# DA_uno_shield_0_2.net
KiCad netlist of a schematic drawn in EAGLE
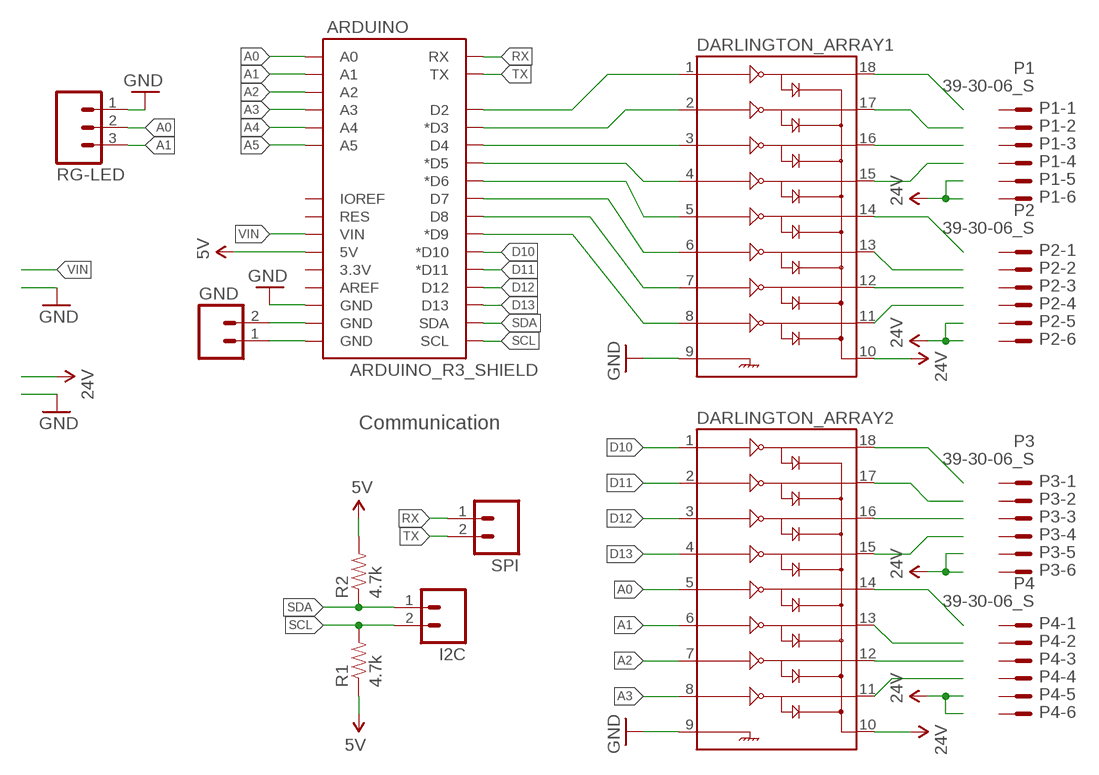
[diagram p0: schematic, sheet 1]

(export (version "E")
  (design (tool "Eeschema 10.0.6"))
  (components
    (comp (ref "ARDUINO")
      (value "ARDUINO_R3_SHIELD")
      (footprint "eagle-import:UNO_R3_SHIELD")
      (libsource (lib "eagle-import") (part "ARDUINO_R3_SHIELD"))
    )
    (comp (ref "DARLINGTON_ARRAY1")
      (value "ULN2803DIP")
      (footprint "eagle-import:DIL18")
      (libsource (lib "eagle-import") (part "ULN2803DIP"))
    )
    (comp (ref "DARLINGTON_ARRAY2")
      (value "ULN2803DIP")
      (footprint "eagle-import:DIL18")
      (libsource (lib "eagle-import") (part "ULN2803DIP"))
    )
    (comp (ref "GND")
      (value "M02LOCK_LONGPADS")
      (footprint "eagle-import:1X02_LOCK_LONGPADS")
      (libsource (lib "eagle-import") (part "M02LOCK_LONGPADS"))
    )
    (comp (ref "I2C")
      (value "M02LOCK_LONGPADS")
      (footprint "eagle-import:1X02_LOCK_LONGPADS")
      (libsource (lib "eagle-import") (part "M02LOCK_LONGPADS"))
    )
    (comp (ref "P1")
      (value "39-30-06_S")
      (footprint "eagle-import:39-30-_06_")
      (libsource (lib "eagle-import") (part "39-30-?06?_S"))
    )
    (comp (ref "P2")
      (value "39-30-06_S")
      (footprint "eagle-import:39-30-_06_")
      (libsource (lib "eagle-import") (part "39-30-?06?_S"))
    )
    (comp (ref "P3")
      (value "39-30-06_S")
      (footprint "eagle-import:39-30-_06_")
      (libsource (lib "eagle-import") (part "39-30-?06?_S"))
    )
    (comp (ref "P4")
      (value "39-30-06_S")
      (footprint "eagle-import:39-30-_06_")
      (libsource (lib "eagle-import") (part "39-30-?06?_S"))
    )
    (comp (ref "R1")
      (value "4.7k")
      (footprint "eagle-import:AXIAL-0.3-KIT")
      (libsource (lib "eagle-import") (part "RESISTORKIT"))
    )
    (comp (ref "R2")
      (value "4.7k")
      (footprint "eagle-import:AXIAL-0.3-KIT")
      (libsource (lib "eagle-import") (part "RESISTORKIT"))
    )
    (comp (ref "RG-LED")
      (value "M03LONGPADS")
      (footprint "eagle-import:1X03_LONGPADS")
      (libsource (lib "eagle-import") (part "M03LONGPADS"))
    )
    (comp (ref "SPI")
      (value "M02LOCK_LONGPADS")
      (footprint "eagle-import:1X02_LOCK_LONGPADS")
      (libsource (lib "eagle-import") (part "M02LOCK_LONGPADS"))
    )
  )
  (nets
    (net (code "1") (name "5V") (class "Default")
      (node (ref "ARDUINO") (pin "5V") (pinfunction "5V_5V") (pintype "bidirectional"))
      (node (ref "R1") (pin "P$1") (pinfunction "1_P$1") (pintype "passive"))
      (node (ref "R2") (pin "P$2") (pinfunction "2_P$2") (pintype "passive"))
    )
    (net (code "2") (name "24V") (class "Default")
      (node (ref "DARLINGTON_ARRAY1") (pin "10") (pinfunction "10_10") (pintype "bidirectional"))
      (node (ref "DARLINGTON_ARRAY2") (pin "10") (pinfunction "10_10") (pintype "bidirectional"))
    )
    (net (code "3") (name "A0") (class "Default")
      (node (ref "ARDUINO") (pin "A0") (pinfunction "A0_A0") (pintype "bidirectional"))
      (node (ref "DARLINGTON_ARRAY2") (pin "5") (pinfunction "5_5") (pintype "bidirectional"))
      (node (ref "RG-LED") (pin "2") (pinfunction "2_2") (pintype "passive"))
    )
    (net (code "4") (name "A1") (class "Default")
      (node (ref "ARDUINO") (pin "A1") (pinfunction "A1_A1") (pintype "bidirectional"))
      (node (ref "DARLINGTON_ARRAY2") (pin "6") (pinfunction "6_6") (pintype "bidirectional"))
      (node (ref "RG-LED") (pin "3") (pinfunction "3_3") (pintype "passive"))
    )
    (net (code "5") (name "A2") (class "Default")
      (node (ref "ARDUINO") (pin "A2") (pinfunction "A2_A2") (pintype "bidirectional"))
      (node (ref "DARLINGTON_ARRAY2") (pin "7") (pinfunction "7_7") (pintype "bidirectional"))
    )
    (net (code "6") (name "A3") (class "Default")
      (node (ref "ARDUINO") (pin "A3") (pinfunction "A3_A3") (pintype "bidirectional"))
      (node (ref "DARLINGTON_ARRAY2") (pin "8") (pinfunction "8_8") (pintype "bidirectional"))
    )
    (net (code "7") (name "A4") (class "Default")
      (node (ref "ARDUINO") (pin "A4") (pinfunction "A4_A4") (pintype "bidirectional"))
    )
    (net (code "8") (name "A5") (class "Default")
      (node (ref "ARDUINO") (pin "A5") (pinfunction "A5_A5") (pintype "bidirectional"))
    )
    (net (code "9") (name "D10") (class "Default")
      (node (ref "ARDUINO") (pin "D10") (pinfunction "*D10_D10") (pintype "bidirectional"))
      (node (ref "DARLINGTON_ARRAY2") (pin "1") (pinfunction "1_1") (pintype "bidirectional"))
    )
    (net (code "10") (name "D11") (class "Default")
      (node (ref "ARDUINO") (pin "D11") (pinfunction "*D11_D11") (pintype "bidirectional"))
      (node (ref "DARLINGTON_ARRAY2") (pin "2") (pinfunction "2_2") (pintype "bidirectional"))
    )
    (net (code "11") (name "D12") (class "Default")
      (node (ref "ARDUINO") (pin "D12") (pinfunction "D12_D12") (pintype "bidirectional"))
      (node (ref "DARLINGTON_ARRAY2") (pin "3") (pinfunction "3_3") (pintype "bidirectional"))
    )
    (net (code "12") (name "D13") (class "Default")
      (node (ref "ARDUINO") (pin "D13") (pinfunction "D13_D13") (pintype "bidirectional"))
      (node (ref "DARLINGTON_ARRAY2") (pin "4") (pinfunction "4_4") (pintype "bidirectional"))
    )
    (net (code "13") (name "GND") (class "Default")
      (node (ref "ARDUINO") (pin "GND@2") (pinfunction "GND_GND@2") (pintype "bidirectional"))
      (node (ref "DARLINGTON_ARRAY1") (pin "9") (pinfunction "9_9") (pintype "bidirectional"))
      (node (ref "DARLINGTON_ARRAY2") (pin "9") (pinfunction "9_9") (pintype "bidirectional"))
      (node (ref "RG-LED") (pin "1") (pinfunction "1_1") (pintype "passive"))
    )
    (net (code "14") (name "Net-(ARDUINO-*D3)") (class "Default")
      (node (ref "ARDUINO") (pin "D3") (pinfunction "*D3_D3") (pintype "bidirectional"))
      (node (ref "DARLINGTON_ARRAY1") (pin "2") (pinfunction "2_2") (pintype "bidirectional"))
    )
    (net (code "15") (name "Net-(ARDUINO-*D5)") (class "Default")
      (node (ref "ARDUINO") (pin "D5") (pinfunction "*D5_D5") (pintype "bidirectional"))
      (node (ref "DARLINGTON_ARRAY1") (pin "4") (pinfunction "4_4") (pintype "bidirectional"))
    )
    (net (code "16") (name "Net-(ARDUINO-*D6)") (class "Default")
      (node (ref "ARDUINO") (pin "D6") (pinfunction "*D6_D6") (pintype "bidirectional"))
      (node (ref "DARLINGTON_ARRAY1") (pin "5") (pinfunction "5_5") (pintype "bidirectional"))
    )
    (net (code "17") (name "Net-(ARDUINO-*D9)") (class "Default")
      (node (ref "ARDUINO") (pin "D9") (pinfunction "*D9_D9") (pintype "bidirectional"))
      (node (ref "DARLINGTON_ARRAY1") (pin "8") (pinfunction "8_8") (pintype "bidirectional"))
    )
    (net (code "18") (name "Net-(ARDUINO-GND-PadGND@0)") (class "Default")
      (node (ref "ARDUINO") (pin "GND@0") (pinfunction "GND_GND@0") (pintype "bidirectional"))
      (node (ref "GND") (pin "1") (pinfunction "1_1") (pintype "passive"))
    )
    (net (code "19") (name "Net-(ARDUINO-GND-PadGND@1)") (class "Default")
      (node (ref "ARDUINO") (pin "GND@1") (pinfunction "GND_GND@1") (pintype "bidirectional"))
      (node (ref "GND") (pin "2") (pinfunction "2_2") (pintype "passive"))
    )
    (net (code "20") (name "Net-(ARDUINO-PadD2)") (class "Default")
      (node (ref "ARDUINO") (pin "D2") (pinfunction "D2_D2") (pintype "bidirectional"))
      (node (ref "DARLINGTON_ARRAY1") (pin "1") (pinfunction "1_1") (pintype "bidirectional"))
    )
    (net (code "21") (name "Net-(ARDUINO-PadD4)") (class "Default")
      (node (ref "ARDUINO") (pin "D4") (pinfunction "D4_D4") (pintype "bidirectional"))
      (node (ref "DARLINGTON_ARRAY1") (pin "3") (pinfunction "3_3") (pintype "bidirectional"))
    )
    (net (code "22") (name "Net-(ARDUINO-PadD7)") (class "Default")
      (node (ref "ARDUINO") (pin "D7") (pinfunction "D7_D7") (pintype "bidirectional"))
      (node (ref "DARLINGTON_ARRAY1") (pin "6") (pinfunction "6_6") (pintype "bidirectional"))
    )
    (net (code "23") (name "Net-(ARDUINO-PadD8)") (class "Default")
      (node (ref "ARDUINO") (pin "D8") (pinfunction "D8_D8") (pintype "bidirectional"))
      (node (ref "DARLINGTON_ARRAY1") (pin "7") (pinfunction "7_7") (pintype "bidirectional"))
    )
    (net (code "24") (name "RX") (class "Default")
      (node (ref "ARDUINO") (pin "RX") (pinfunction "RX_RX") (pintype "bidirectional"))
      (node (ref "SPI") (pin "1") (pinfunction "1_1") (pintype "passive"))
    )
    (net (code "25") (name "SCL") (class "Default")
      (node (ref "ARDUINO") (pin "SCL") (pinfunction "SCL_SCL") (pintype "bidirectional"))
      (node (ref "I2C") (pin "2") (pinfunction "2_2") (pintype "passive"))
      (node (ref "R1") (pin "P$2") (pinfunction "2_P$2") (pintype "passive"))
    )
    (net (code "26") (name "SDA") (class "Default")
      (node (ref "ARDUINO") (pin "SDA") (pinfunction "SDA_SDA") (pintype "bidirectional"))
      (node (ref "I2C") (pin "1") (pinfunction "1_1") (pintype "passive"))
      (node (ref "R2") (pin "P$1") (pinfunction "1_P$1") (pintype "passive"))
    )
    (net (code "27") (name "TX") (class "Default")
      (node (ref "ARDUINO") (pin "TX") (pinfunction "TX_TX") (pintype "bidirectional"))
      (node (ref "SPI") (pin "2") (pinfunction "2_2") (pintype "passive"))
    )
    (net (code "28") (name "VIN") (class "Default")
      (node (ref "ARDUINO") (pin "VIN") (pinfunction "VIN_VIN") (pintype "bidirectional"))
    )
    (net (code "29") (name "unconnected-(ARDUINO-Pad3.3V)") (class "Default")
      (node (ref "ARDUINO") (pin "3.3V") (pinfunction "3.3V_3.3V") (pintype "bidirectional"))
    )
    (net (code "30") (name "unconnected-(ARDUINO-PadAREF)") (class "Default")
      (node (ref "ARDUINO") (pin "AREF") (pinfunction "AREF_AREF") (pintype "bidirectional"))
    )
    (net (code "31") (name "unconnected-(ARDUINO-PadIOREF)") (class "Default")
      (node (ref "ARDUINO") (pin "IOREF") (pinfunction "IOREF_IOREF") (pintype "bidirectional"))
    )
    (net (code "32") (name "unconnected-(ARDUINO-PadRES)") (class "Default")
      (node (ref "ARDUINO") (pin "RES") (pinfunction "RES_RES") (pintype "bidirectional"))
    )
    (net (code "33") (name "unconnected-(DARLINGTON_ARRAY1-Pad11)") (class "Default")
      (node (ref "DARLINGTON_ARRAY1") (pin "11") (pinfunction "11_11") (pintype "bidirectional"))
    )
    (net (code "34") (name "unconnected-(DARLINGTON_ARRAY1-Pad12)") (class "Default")
      (node (ref "DARLINGTON_ARRAY1") (pin "12") (pinfunction "12_12") (pintype "bidirectional"))
    )
    (net (code "35") (name "unconnected-(DARLINGTON_ARRAY1-Pad13)") (class "Default")
      (node (ref "DARLINGTON_ARRAY1") (pin "13") (pinfunction "13_13") (pintype "bidirectional"))
    )
    (net (code "36") (name "unconnected-(DARLINGTON_ARRAY1-Pad14)") (class "Default")
      (node (ref "DARLINGTON_ARRAY1") (pin "14") (pinfunction "14_14") (pintype "bidirectional"))
    )
    (net (code "37") (name "unconnected-(DARLINGTON_ARRAY1-Pad15)") (class "Default")
      (node (ref "DARLINGTON_ARRAY1") (pin "15") (pinfunction "15_15") (pintype "bidirectional"))
    )
    (net (code "38") (name "unconnected-(DARLINGTON_ARRAY1-Pad16)") (class "Default")
      (node (ref "DARLINGTON_ARRAY1") (pin "16") (pinfunction "16_16") (pintype "bidirectional"))
    )
    (net (code "39") (name "unconnected-(DARLINGTON_ARRAY1-Pad17)") (class "Default")
      (node (ref "DARLINGTON_ARRAY1") (pin "17") (pinfunction "17_17") (pintype "bidirectional"))
    )
    (net (code "40") (name "unconnected-(DARLINGTON_ARRAY1-Pad18)") (class "Default")
      (node (ref "DARLINGTON_ARRAY1") (pin "18") (pinfunction "18_18") (pintype "bidirectional"))
    )
    (net (code "41") (name "unconnected-(DARLINGTON_ARRAY2-Pad11)") (class "Default")
      (node (ref "DARLINGTON_ARRAY2") (pin "11") (pinfunction "11_11") (pintype "bidirectional"))
    )
    (net (code "42") (name "unconnected-(DARLINGTON_ARRAY2-Pad12)") (class "Default")
      (node (ref "DARLINGTON_ARRAY2") (pin "12") (pinfunction "12_12") (pintype "bidirectional"))
    )
    (net (code "43") (name "unconnected-(DARLINGTON_ARRAY2-Pad13)") (class "Default")
      (node (ref "DARLINGTON_ARRAY2") (pin "13") (pinfunction "13_13") (pintype "bidirectional"))
    )
    (net (code "44") (name "unconnected-(DARLINGTON_ARRAY2-Pad14)") (class "Default")
      (node (ref "DARLINGTON_ARRAY2") (pin "14") (pinfunction "14_14") (pintype "bidirectional"))
    )
    (net (code "45") (name "unconnected-(DARLINGTON_ARRAY2-Pad15)") (class "Default")
      (node (ref "DARLINGTON_ARRAY2") (pin "15") (pinfunction "15_15") (pintype "bidirectional"))
    )
    (net (code "46") (name "unconnected-(DARLINGTON_ARRAY2-Pad16)") (class "Default")
      (node (ref "DARLINGTON_ARRAY2") (pin "16") (pinfunction "16_16") (pintype "bidirectional"))
    )
    (net (code "47") (name "unconnected-(DARLINGTON_ARRAY2-Pad17)") (class "Default")
      (node (ref "DARLINGTON_ARRAY2") (pin "17") (pinfunction "17_17") (pintype "bidirectional"))
    )
    (net (code "48") (name "unconnected-(DARLINGTON_ARRAY2-Pad18)") (class "Default")
      (node (ref "DARLINGTON_ARRAY2") (pin "18") (pinfunction "18_18") (pintype "bidirectional"))
    )
    (net (code "49") (name "unconnected-(P1A-P-Pad1)") (class "Default")
      (node (ref "P1") (pin "1") (pinfunction "P_1") (pintype "passive"))
    )
    (net (code "50") (name "unconnected-(P1B-P-Pad2)") (class "Default")
      (node (ref "P1") (pin "2") (pinfunction "P_2") (pintype "passive"))
    )
    (net (code "51") (name "unconnected-(P1C-P-Pad3)") (class "Default")
      (node (ref "P1") (pin "3") (pinfunction "P_3") (pintype "passive"))
    )
    (net (code "52") (name "unconnected-(P1D-P-Pad4)") (class "Default")
      (node (ref "P1") (pin "4") (pinfunction "P_4") (pintype "passive"))
    )
    (net (code "53") (name "unconnected-(P1E-P-Pad5)") (class "Default")
      (node (ref "P1") (pin "5") (pinfunction "P_5") (pintype "passive"))
    )
    (net (code "54") (name "unconnected-(P1F-P-Pad6)") (class "Default")
      (node (ref "P1") (pin "6") (pinfunction "P_6") (pintype "passive"))
    )
    (net (code "55") (name "unconnected-(P2A-P-Pad1)") (class "Default")
      (node (ref "P2") (pin "1") (pinfunction "P_1") (pintype "passive"))
    )
    (net (code "56") (name "unconnected-(P2B-P-Pad2)") (class "Default")
      (node (ref "P2") (pin "2") (pinfunction "P_2") (pintype "passive"))
    )
    (net (code "57") (name "unconnected-(P2C-P-Pad3)") (class "Default")
      (node (ref "P2") (pin "3") (pinfunction "P_3") (pintype "passive"))
    )
    (net (code "58") (name "unconnected-(P2D-P-Pad4)") (class "Default")
      (node (ref "P2") (pin "4") (pinfunction "P_4") (pintype "passive"))
    )
    (net (code "59") (name "unconnected-(P2E-P-Pad5)") (class "Default")
      (node (ref "P2") (pin "5") (pinfunction "P_5") (pintype "passive"))
    )
    (net (code "60") (name "unconnected-(P2F-P-Pad6)") (class "Default")
      (node (ref "P2") (pin "6") (pinfunction "P_6") (pintype "passive"))
    )
    (net (code "61") (name "unconnected-(P3A-P-Pad1)") (class "Default")
      (node (ref "P3") (pin "1") (pinfunction "P_1") (pintype "passive"))
    )
    (net (code "62") (name "unconnected-(P3B-P-Pad2)") (class "Default")
      (node (ref "P3") (pin "2") (pinfunction "P_2") (pintype "passive"))
    )
    (net (code "63") (name "unconnected-(P3C-P-Pad3)") (class "Default")
      (node (ref "P3") (pin "3") (pinfunction "P_3") (pintype "passive"))
    )
    (net (code "64") (name "unconnected-(P3D-P-Pad4)") (class "Default")
      (node (ref "P3") (pin "4") (pinfunction "P_4") (pintype "passive"))
    )
    (net (code "65") (name "unconnected-(P3E-P-Pad5)") (class "Default")
      (node (ref "P3") (pin "5") (pinfunction "P_5") (pintype "passive"))
    )
    (net (code "66") (name "unconnected-(P3F-P-Pad6)") (class "Default")
      (node (ref "P3") (pin "6") (pinfunction "P_6") (pintype "passive"))
    )
    (net (code "67") (name "unconnected-(P4A-P-Pad1)") (class "Default")
      (node (ref "P4") (pin "1") (pinfunction "P_1") (pintype "passive"))
    )
    (net (code "68") (name "unconnected-(P4B-P-Pad2)") (class "Default")
      (node (ref "P4") (pin "2") (pinfunction "P_2") (pintype "passive"))
    )
    (net (code "69") (name "unconnected-(P4C-P-Pad3)") (class "Default")
      (node (ref "P4") (pin "3") (pinfunction "P_3") (pintype "passive"))
    )
    (net (code "70") (name "unconnected-(P4D-P-Pad4)") (class "Default")
      (node (ref "P4") (pin "4") (pinfunction "P_4") (pintype "passive"))
    )
    (net (code "71") (name "unconnected-(P4E-P-Pad5)") (class "Default")
      (node (ref "P4") (pin "5") (pinfunction "P_5") (pintype "passive"))
    )
    (net (code "72") (name "unconnected-(P4F-P-Pad6)") (class "Default")
      (node (ref "P4") (pin "6") (pinfunction "P_6") (pintype "passive"))
    )
  )
)
